# Connector_Inverter.net
KiCad netlist of a schematic drawn in Altium Designer
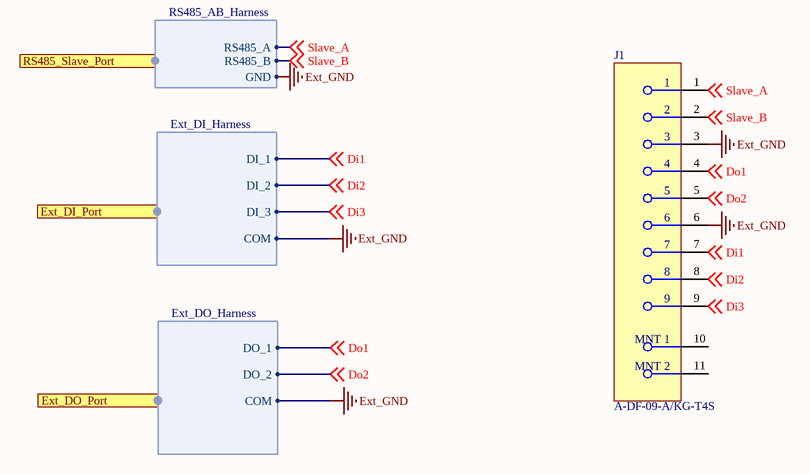
[diagram p0: Connector_Inverter.SchDoc]

(export (version "E")
  (design (tool "Eeschema 10.0.6"))
  (components
    (comp (ref "J1")
      (value "A-DF-09-A/KG-T4S")
      (footprint "FP-A-DF_09_A-KG-T4S-MFG")
      (description "Conn D-Sub F 9 POS 1.38mm Solder RA Thru-Hole 9 Terminal 1 Port")
      (fields (field (name "DIGI-KEY_PART_NUMBER") "AE10924-ND"))
      (libsource (lib "Altium Content Vault") (part "A-DF_09_A-KG-T4S"))
    )
  )
  (nets
    (net (code "7") (name "Di1") (class "Default")
      (node (ref "J1") (pin "7") (pinfunction "7_7") (pintype "passive"))
    )
    (net (code "8") (name "Di2") (class "Default")
      (node (ref "J1") (pin "8") (pinfunction "8_8") (pintype "passive"))
    )
    (net (code "9") (name "Di3") (class "Default")
      (node (ref "J1") (pin "9") (pinfunction "9_9") (pintype "passive"))
    )
    (net (code "10") (name "Do1") (class "Default")
      (node (ref "J1") (pin "4") (pinfunction "4_4") (pintype "passive"))
    )
    (net (code "11") (name "Do2") (class "Default")
      (node (ref "J1") (pin "5") (pinfunction "5_5") (pintype "passive"))
    )
    (net (code "12") (name "Ext_GND") (class "Default")
      (node (ref "J1") (pin "3") (pinfunction "3_3") (pintype "passive"))
      (node (ref "J1") (pin "6") (pinfunction "6_6") (pintype "passive"))
    )
    (net (code "13") (name "Slave_A") (class "Default")
      (node (ref "J1") (pin "1") (pinfunction "1_1") (pintype "passive"))
    )
    (net (code "14") (name "Slave_B") (class "Default")
      (node (ref "J1") (pin "2") (pinfunction "2_2") (pintype "passive"))
    )
    (net (code "15") (name "unconnected-(J1-MNT_1-Pad10)") (class "Default")
      (node (ref "J1") (pin "10") (pinfunction "MNT_1_10") (pintype "passive"))
    )
    (net (code "16") (name "unconnected-(J1-MNT_2-Pad11)") (class "Default")
      (node (ref "J1") (pin "11") (pinfunction "MNT_2_11") (pintype "passive"))
    )
  )
)
